# auxiliary.net
KiCad netlist of a schematic drawn in EAGLE
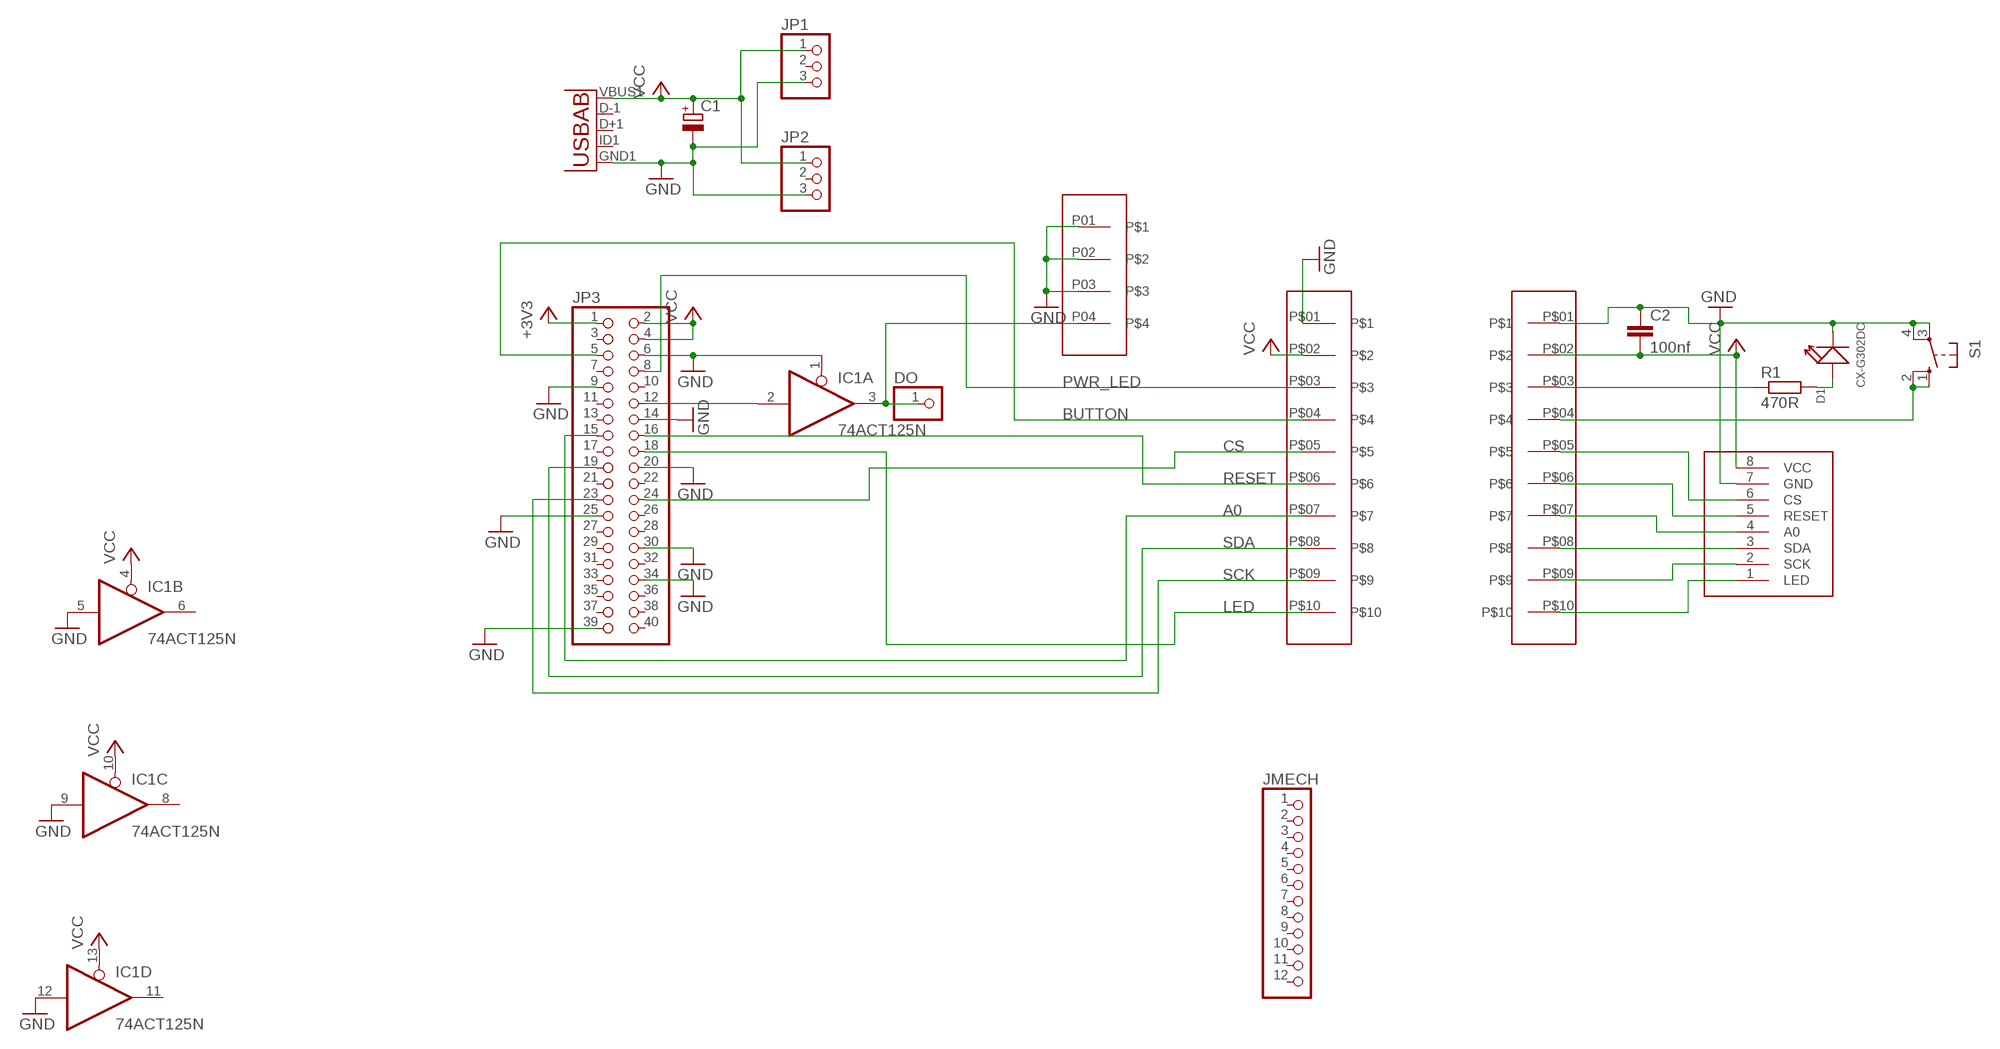
[diagram p0: schematic, sheet 1]

(export (version "E")
  (design (tool "Eeschema 10.0.6"))
  (components
    (comp (ref "C1")
      (value "CPOL-EUE5-10.5")
      (footprint "eagle-import:E5-10,5")
      (libsource (lib "eagle-import") (part "CPOL-EUE5-10.5"))
    )
    (comp (ref "C2")
      (value "100nf")
      (footprint "eagle-import:C025-030X050")
      (libsource (lib "eagle-import") (part "C-EU025-030X050"))
    )
    (comp (ref "D1")
      (value "CX-G302DC")
      (footprint "eagle-import:LED2-2.54-D3.0MM")
      (libsource (lib "eagle-import") (part "DIP-LED-GREEN-GREEN(2P-D3MM)"))
    )
    (comp (ref "DO")
      (value "PINHD-1X1")
      (footprint "eagle-import:1X01")
      (libsource (lib "eagle-import") (part "PINHD-1X1"))
    )
    (comp (ref "IC1")
      (value "74ACT125N")
      (footprint "eagle-import:DIL14")
      (libsource (lib "eagle-import") (part "74125NACT"))
    )
    (comp (ref "J1")
      (value "JST1.25_10PIN")
      (footprint "eagle-import:JST1.25_10PIN")
      (libsource (lib "eagle-import") (part "JST1.25_10PIN"))
    )
    (comp (ref "J2")
      (value "JST1.25_10PIN")
      (footprint "eagle-import:JST1.25_10PIN")
      (libsource (lib "eagle-import") (part "JST1.25_10PIN"))
    )
    (comp (ref "JMECH")
      (value "PINHD-1X12")
      (footprint "eagle-import:1X12")
      (libsource (lib "eagle-import") (part "PINHD-1X12"))
    )
    (comp (ref "JP1")
      (value "PINHD-1X3")
      (footprint "eagle-import:1X03")
      (libsource (lib "eagle-import") (part "PINHD-1X3"))
    )
    (comp (ref "JP2")
      (value "PINHD-1X3")
      (footprint "eagle-import:1X03")
      (libsource (lib "eagle-import") (part "PINHD-1X3"))
    )
    (comp (ref "JP3")
      (value "PINHD-2X20")
      (footprint "eagle-import:2X20")
      (libsource (lib "eagle-import") (part "PINHD-2X20"))
    )
    (comp (ref "R1")
      (value "470R")
      (footprint "eagle-import:0207_7")
      (libsource (lib "eagle-import") (part "R-EU_0207/7"))
    )
    (comp (ref "S1")
      (value "10-XX")
      (footprint "eagle-import:B3F-10XX")
      (fields (field (name "MPN") "B3F-1000"))
      (libsource (lib "eagle-import") (part "10-XX"))
    )
    (comp (ref "U$2")
      (value "SPI_TFT_1.44\"")
      (footprint "eagle-import:SPI_TFT_1.44_")
      (libsource (lib "eagle-import") (part "SPI_TFT_1.44{dblquote}"))
    )
    (comp (ref "U$3")
      (value "JST1.25_4PIN")
      (footprint "eagle-import:JST1.25_4PIN")
      (libsource (lib "eagle-import") (part "JST1.25_4PIN"))
    )
    (comp (ref "U1")
      (value "USB-THROUGH")
      (footprint "eagle-import:USB-MICRO-THROUGH")
      (libsource (lib "eagle-import") (part "USB-THROUGH"))
    )
  )
  (nets
    (net (code "1") (name "+3V3") (class "Default")
      (node (ref "JP3") (pin "1") (pinfunction "1_1") (pintype "passive"))
    )
    (net (code "2") (name "/A0") (class "Default")
      (node (ref "J1") (pin "P$07") (pinfunction "P$7_P$07") (pintype "bidirectional"))
      (node (ref "JP3") (pin "15") (pinfunction "15_15") (pintype "passive"))
    )
    (net (code "3") (name "/BUTTON") (class "Default")
      (node (ref "J1") (pin "P$04") (pinfunction "P$4_P$04") (pintype "bidirectional"))
      (node (ref "JP3") (pin "5") (pinfunction "5_5") (pintype "passive"))
    )
    (net (code "4") (name "/CS") (class "Default")
      (node (ref "J1") (pin "P$05") (pinfunction "P$5_P$05") (pintype "bidirectional"))
      (node (ref "JP3") (pin "24") (pinfunction "24_24") (pintype "passive"))
    )
    (net (code "5") (name "/LED") (class "Default")
      (node (ref "J1") (pin "P$10") (pinfunction "P$10_P$10") (pintype "bidirectional"))
      (node (ref "JP3") (pin "18") (pinfunction "18_18") (pintype "passive"))
    )
    (net (code "6") (name "/PWR_LED") (class "Default")
      (node (ref "J1") (pin "P$03") (pinfunction "P$3_P$03") (pintype "bidirectional"))
      (node (ref "JP3") (pin "8") (pinfunction "8_8") (pintype "passive"))
    )
    (net (code "7") (name "/RESET") (class "Default")
      (node (ref "J1") (pin "P$06") (pinfunction "P$6_P$06") (pintype "bidirectional"))
      (node (ref "JP3") (pin "16") (pinfunction "16_16") (pintype "passive"))
    )
    (net (code "8") (name "/SCK") (class "Default")
      (node (ref "J1") (pin "P$09") (pinfunction "P$9_P$09") (pintype "bidirectional"))
      (node (ref "JP3") (pin "23") (pinfunction "23_23") (pintype "passive"))
    )
    (net (code "9") (name "/SDA") (class "Default")
      (node (ref "J1") (pin "P$08") (pinfunction "P$8_P$08") (pintype "bidirectional"))
      (node (ref "JP3") (pin "19") (pinfunction "19_19") (pintype "passive"))
    )
    (net (code "10") (name "GND") (class "Default")
      (node (ref "C1") (pin "-") (pinfunction "-_-") (pintype "passive"))
      (node (ref "C2") (pin "1") (pinfunction "1_1") (pintype "passive"))
      (node (ref "D1") (pin "K") (pinfunction "-_K") (pintype "passive"))
      (node (ref "IC1") (pin "1") (pinfunction "OE_1") (pintype "input"))
      (node (ref "IC1") (pin "12") (pinfunction "I_12") (pintype "input"))
      (node (ref "IC1") (pin "5") (pinfunction "I_5") (pintype "input"))
      (node (ref "IC1") (pin "9") (pinfunction "I_9") (pintype "input"))
      (node (ref "J1") (pin "P$01") (pinfunction "P$1_P$01") (pintype "bidirectional"))
      (node (ref "J2") (pin "P$01") (pinfunction "P$1_P$01") (pintype "bidirectional"))
      (node (ref "JP1") (pin "3") (pinfunction "3_3") (pintype "passive"))
      (node (ref "JP2") (pin "3") (pinfunction "3_3") (pintype "passive"))
      (node (ref "JP3") (pin "14") (pinfunction "14_14") (pintype "passive"))
      (node (ref "JP3") (pin "20") (pinfunction "20_20") (pintype "passive"))
      (node (ref "JP3") (pin "25") (pinfunction "25_25") (pintype "passive"))
      (node (ref "JP3") (pin "30") (pinfunction "30_30") (pintype "passive"))
      (node (ref "JP3") (pin "34") (pinfunction "34_34") (pintype "passive"))
      (node (ref "JP3") (pin "39") (pinfunction "39_39") (pintype "passive"))
      (node (ref "JP3") (pin "6") (pinfunction "6_6") (pintype "passive"))
      (node (ref "JP3") (pin "9") (pinfunction "9_9") (pintype "passive"))
      (node (ref "S1") (pin "3") (pinfunction "P_3") (pintype "passive"))
      (node (ref "S1") (pin "4") (pinfunction "P1_4") (pintype "passive"))
      (node (ref "U$2") (pin "7") (pinfunction "GND_7") (pintype "power_in"))
      (node (ref "U$3") (pin "P01") (pinfunction "P$1_P01") (pintype "bidirectional"))
      (node (ref "U$3") (pin "P02") (pinfunction "P$2_P02") (pintype "bidirectional"))
      (node (ref "U$3") (pin "P03") (pinfunction "P$3_P03") (pintype "bidirectional"))
      (node (ref "U1") (pin "GND1") (pinfunction "GND_GND1") (pintype "bidirectional"))
    )
    (net (code "11") (name "Net-(D1-+)") (class "Default")
      (node (ref "D1") (pin "A") (pinfunction "+_A") (pintype "passive"))
      (node (ref "R1") (pin "2") (pinfunction "2_2") (pintype "passive"))
    )
    (net (code "12") (name "Net-(IC1A-I)") (class "Default")
      (node (ref "IC1") (pin "2") (pinfunction "I_2") (pintype "input"))
      (node (ref "JP3") (pin "12") (pinfunction "12_12") (pintype "passive"))
    )
    (net (code "13") (name "Net-(IC1A-O)") (class "Default")
      (node (ref "DO") (pin "1") (pinfunction "1_1") (pintype "passive"))
      (node (ref "IC1") (pin "3") (pinfunction "O_3") (pintype "tri_state"))
      (node (ref "U$3") (pin "P04") (pinfunction "P$4_P04") (pintype "bidirectional"))
    )
    (net (code "14") (name "Net-(J2-P$3)") (class "Default")
      (node (ref "J2") (pin "P$03") (pinfunction "P$3_P$03") (pintype "bidirectional"))
      (node (ref "R1") (pin "1") (pinfunction "1_1") (pintype "passive"))
    )
    (net (code "15") (name "Net-(J2-P$4)") (class "Default")
      (node (ref "J2") (pin "P$04") (pinfunction "P$4_P$04") (pintype "bidirectional"))
      (node (ref "S1") (pin "1") (pinfunction "S_1") (pintype "passive"))
      (node (ref "S1") (pin "2") (pinfunction "S1_2") (pintype "passive"))
    )
    (net (code "16") (name "Net-(J2-P$5)") (class "Default")
      (node (ref "J2") (pin "P$05") (pinfunction "P$5_P$05") (pintype "bidirectional"))
      (node (ref "U$2") (pin "6") (pinfunction "CS_6") (pintype "bidirectional"))
    )
    (net (code "17") (name "Net-(J2-P$6)") (class "Default")
      (node (ref "J2") (pin "P$06") (pinfunction "P$6_P$06") (pintype "bidirectional"))
      (node (ref "U$2") (pin "5") (pinfunction "RESET_5") (pintype "bidirectional"))
    )
    (net (code "18") (name "Net-(J2-P$7)") (class "Default")
      (node (ref "J2") (pin "P$07") (pinfunction "P$7_P$07") (pintype "bidirectional"))
      (node (ref "U$2") (pin "4") (pinfunction "A0_4") (pintype "bidirectional"))
    )
    (net (code "19") (name "Net-(J2-P$8)") (class "Default")
      (node (ref "J2") (pin "P$08") (pinfunction "P$8_P$08") (pintype "bidirectional"))
      (node (ref "U$2") (pin "3") (pinfunction "SDA_3") (pintype "bidirectional"))
    )
    (net (code "20") (name "Net-(J2-P$9)") (class "Default")
      (node (ref "J2") (pin "P$09") (pinfunction "P$9_P$09") (pintype "bidirectional"))
      (node (ref "U$2") (pin "2") (pinfunction "SCK_2") (pintype "bidirectional"))
    )
    (net (code "21") (name "Net-(U$2-LED)") (class "Default")
      (node (ref "J2") (pin "P$10") (pinfunction "P$10_P$10") (pintype "bidirectional"))
      (node (ref "U$2") (pin "1") (pinfunction "LED_1") (pintype "bidirectional"))
    )
    (net (code "22") (name "VCC") (class "Default")
      (node (ref "C1") (pin "+") (pinfunction "+_+") (pintype "passive"))
      (node (ref "C2") (pin "2") (pinfunction "2_2") (pintype "passive"))
      (node (ref "IC1") (pin "10") (pinfunction "OE_10") (pintype "input"))
      (node (ref "IC1") (pin "13") (pinfunction "OE_13") (pintype "input"))
      (node (ref "IC1") (pin "4") (pinfunction "OE_4") (pintype "input"))
      (node (ref "J1") (pin "P$02") (pinfunction "P$2_P$02") (pintype "bidirectional"))
      (node (ref "J2") (pin "P$02") (pinfunction "P$2_P$02") (pintype "bidirectional"))
      (node (ref "JP1") (pin "1") (pinfunction "1_1") (pintype "passive"))
      (node (ref "JP2") (pin "1") (pinfunction "1_1") (pintype "passive"))
      (node (ref "JP3") (pin "2") (pinfunction "2_2") (pintype "passive"))
      (node (ref "JP3") (pin "4") (pinfunction "4_4") (pintype "passive"))
      (node (ref "U$2") (pin "8") (pinfunction "VCC_8") (pintype "power_in"))
      (node (ref "U1") (pin "VBUS1") (pinfunction "VBUS_VBUS1") (pintype "bidirectional"))
    )
    (net (code "23") (name "unconnected-(IC1B-O-Pad6)") (class "Default")
      (node (ref "IC1") (pin "6") (pinfunction "O_6") (pintype "tri_state"))
    )
    (net (code "24") (name "unconnected-(IC1C-O-Pad8)") (class "Default")
      (node (ref "IC1") (pin "8") (pinfunction "O_8") (pintype "tri_state"))
    )
    (net (code "25") (name "unconnected-(IC1D-O-Pad11)") (class "Default")
      (node (ref "IC1") (pin "11") (pinfunction "O_11") (pintype "tri_state"))
    )
    (net (code "26") (name "unconnected-(JMECH-Pad1)") (class "Default")
      (node (ref "JMECH") (pin "1") (pinfunction "1_1") (pintype "passive"))
    )
    (net (code "27") (name "unconnected-(JMECH-Pad2)") (class "Default")
      (node (ref "JMECH") (pin "2") (pinfunction "2_2") (pintype "passive"))
    )
    (net (code "28") (name "unconnected-(JMECH-Pad3)") (class "Default")
      (node (ref "JMECH") (pin "3") (pinfunction "3_3") (pintype "passive"))
    )
    (net (code "29") (name "unconnected-(JMECH-Pad4)") (class "Default")
      (node (ref "JMECH") (pin "4") (pinfunction "4_4") (pintype "passive"))
    )
    (net (code "30") (name "unconnected-(JMECH-Pad5)") (class "Default")
      (node (ref "JMECH") (pin "5") (pinfunction "5_5") (pintype "passive"))
    )
    (net (code "31") (name "unconnected-(JMECH-Pad6)") (class "Default")
      (node (ref "JMECH") (pin "6") (pinfunction "6_6") (pintype "passive"))
    )
    (net (code "32") (name "unconnected-(JMECH-Pad7)") (class "Default")
      (node (ref "JMECH") (pin "7") (pinfunction "7_7") (pintype "passive"))
    )
    (net (code "33") (name "unconnected-(JMECH-Pad8)") (class "Default")
      (node (ref "JMECH") (pin "8") (pinfunction "8_8") (pintype "passive"))
    )
    (net (code "34") (name "unconnected-(JMECH-Pad9)") (class "Default")
      (node (ref "JMECH") (pin "9") (pinfunction "9_9") (pintype "passive"))
    )
    (net (code "35") (name "unconnected-(JMECH-Pad10)") (class "Default")
      (node (ref "JMECH") (pin "10") (pinfunction "10_10") (pintype "passive"))
    )
    (net (code "36") (name "unconnected-(JMECH-Pad11)") (class "Default")
      (node (ref "JMECH") (pin "11") (pinfunction "11_11") (pintype "passive"))
    )
    (net (code "37") (name "unconnected-(JMECH-Pad12)") (class "Default")
      (node (ref "JMECH") (pin "12") (pinfunction "12_12") (pintype "passive"))
    )
    (net (code "38") (name "unconnected-(JP1-Pad2)") (class "Default")
      (node (ref "JP1") (pin "2") (pinfunction "2_2") (pintype "passive"))
    )
    (net (code "39") (name "unconnected-(JP2-Pad2)") (class "Default")
      (node (ref "JP2") (pin "2") (pinfunction "2_2") (pintype "passive"))
    )
    (net (code "40") (name "unconnected-(JP3-Pad3)") (class "Default")
      (node (ref "JP3") (pin "3") (pinfunction "3_3") (pintype "passive"))
    )
    (net (code "41") (name "unconnected-(JP3-Pad7)") (class "Default")
      (node (ref "JP3") (pin "7") (pinfunction "7_7") (pintype "passive"))
    )
    (net (code "42") (name "unconnected-(JP3-Pad10)") (class "Default")
      (node (ref "JP3") (pin "10") (pinfunction "10_10") (pintype "passive"))
    )
    (net (code "43") (name "unconnected-(JP3-Pad11)") (class "Default")
      (node (ref "JP3") (pin "11") (pinfunction "11_11") (pintype "passive"))
    )
    (net (code "44") (name "unconnected-(JP3-Pad13)") (class "Default")
      (node (ref "JP3") (pin "13") (pinfunction "13_13") (pintype "passive"))
    )
    (net (code "45") (name "unconnected-(JP3-Pad17)") (class "Default")
      (node (ref "JP3") (pin "17") (pinfunction "17_17") (pintype "passive"))
    )
    (net (code "46") (name "unconnected-(JP3-Pad21)") (class "Default")
      (node (ref "JP3") (pin "21") (pinfunction "21_21") (pintype "passive"))
    )
    (net (code "47") (name "unconnected-(JP3-Pad22)") (class "Default")
      (node (ref "JP3") (pin "22") (pinfunction "22_22") (pintype "passive"))
    )
    (net (code "48") (name "unconnected-(JP3-Pad26)") (class "Default")
      (node (ref "JP3") (pin "26") (pinfunction "26_26") (pintype "passive"))
    )
    (net (code "49") (name "unconnected-(JP3-Pad27)") (class "Default")
      (node (ref "JP3") (pin "27") (pinfunction "27_27") (pintype "passive"))
    )
    (net (code "50") (name "unconnected-(JP3-Pad28)") (class "Default")
      (node (ref "JP3") (pin "28") (pinfunction "28_28") (pintype "passive"))
    )
    (net (code "51") (name "unconnected-(JP3-Pad29)") (class "Default")
      (node (ref "JP3") (pin "29") (pinfunction "29_29") (pintype "passive"))
    )
    (net (code "52") (name "unconnected-(JP3-Pad31)") (class "Default")
      (node (ref "JP3") (pin "31") (pinfunction "31_31") (pintype "passive"))
    )
    (net (code "53") (name "unconnected-(JP3-Pad32)") (class "Default")
      (node (ref "JP3") (pin "32") (pinfunction "32_32") (pintype "passive"))
    )
    (net (code "54") (name "unconnected-(JP3-Pad33)") (class "Default")
      (node (ref "JP3") (pin "33") (pinfunction "33_33") (pintype "passive"))
    )
    (net (code "55") (name "unconnected-(JP3-Pad35)") (class "Default")
      (node (ref "JP3") (pin "35") (pinfunction "35_35") (pintype "passive"))
    )
    (net (code "56") (name "unconnected-(JP3-Pad36)") (class "Default")
      (node (ref "JP3") (pin "36") (pinfunction "36_36") (pintype "passive"))
    )
    (net (code "57") (name "unconnected-(JP3-Pad37)") (class "Default")
      (node (ref "JP3") (pin "37") (pinfunction "37_37") (pintype "passive"))
    )
    (net (code "58") (name "unconnected-(JP3-Pad38)") (class "Default")
      (node (ref "JP3") (pin "38") (pinfunction "38_38") (pintype "passive"))
    )
    (net (code "59") (name "unconnected-(JP3-Pad40)") (class "Default")
      (node (ref "JP3") (pin "40") (pinfunction "40_40") (pintype "passive"))
    )
    (net (code "60") (name "unconnected-(U1-D+-PadD+1)") (class "Default")
      (node (ref "U1") (pin "D+1") (pinfunction "D+_D+1") (pintype "bidirectional"))
    )
    (net (code "61") (name "unconnected-(U1-D--PadD-1)") (class "Default")
      (node (ref "U1") (pin "D-1") (pinfunction "D-_D-1") (pintype "bidirectional"))
    )
    (net (code "62") (name "unconnected-(U1-USBID-PadID1)") (class "Default")
      (node (ref "U1") (pin "ID1") (pinfunction "USBID_ID1") (pintype "bidirectional"))
    )
  )
)
